# Test_Eagle_File_Sch.net
KiCad netlist of a schematic drawn in EAGLE
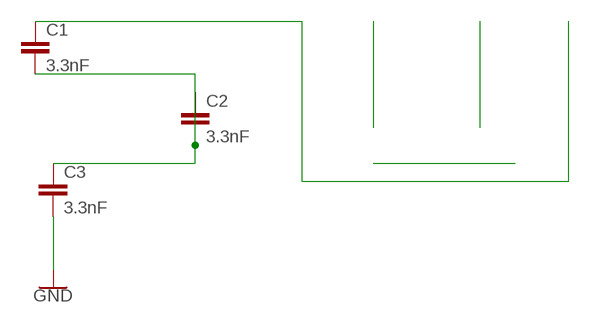
[diagram p0: schematic, sheet 1]
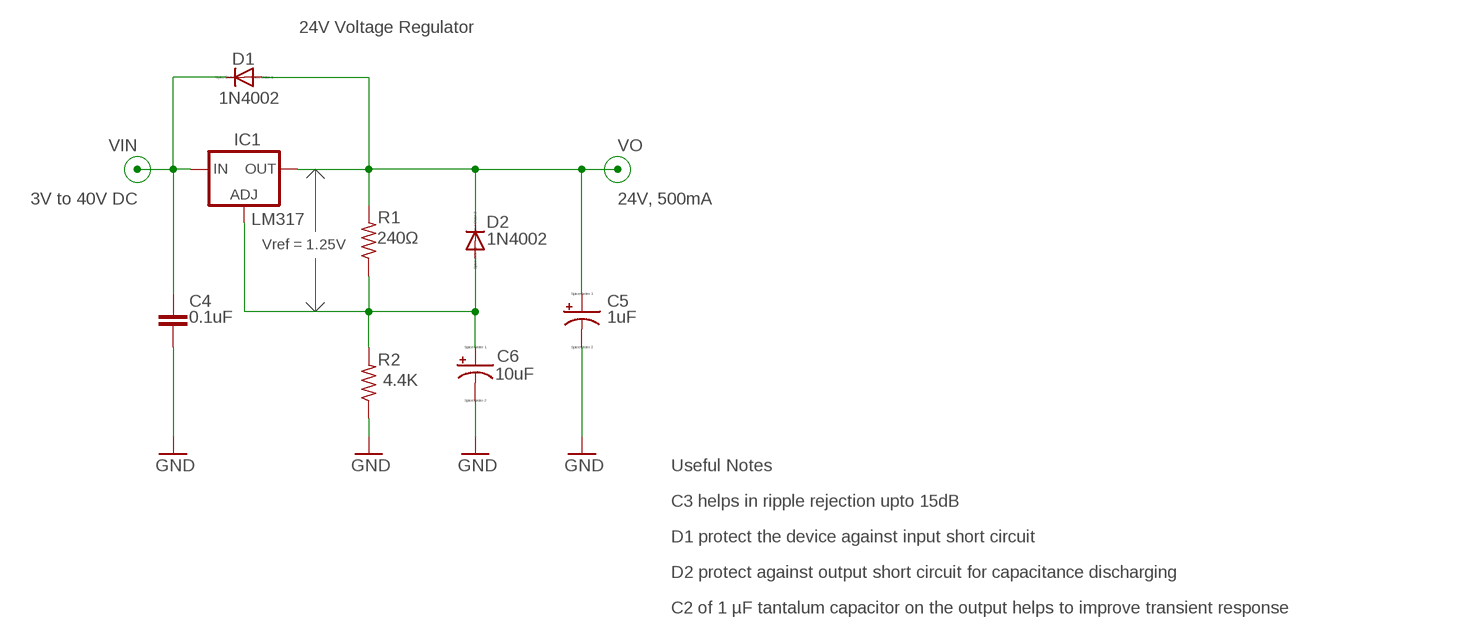
[diagram p1: schematic, sheet 2]

(export (version "E")
  (design (tool "Eeschema 10.0.6"))
  (components
    (comp (ref "C4")
      (value "0.1uF")
      (footprint "eagle-import:C075-052X106")
      (libsource (lib "eagle-import") (part "C-EU075-052X106"))
    )
    (comp (ref "C5")
      (value "1uF")
      (footprint "eagle-import:085CS_1AR")
      (libsource (lib "eagle-import") (part "CPOL-US085CS-1AR"))
    )
    (comp (ref "C6")
      (value "10uF")
      (footprint "eagle-import:085CS_1AR")
      (libsource (lib "eagle-import") (part "CPOL-US085CS-1AR"))
    )
    (comp (ref "D1")
      (value "1N4002")
      (footprint "eagle-import:DO41-10")
      (libsource (lib "eagle-import") (part "1N4004"))
    )
    (comp (ref "D2")
      (value "1N4002")
      (footprint "eagle-import:DO41-10")
      (libsource (lib "eagle-import") (part "1N4004"))
    )
    (comp (ref "IC1")
      (value "LM317MBSTT3")
      (footprint "eagle-import:SOT223")
      (fields (field (name "PARTNUMBER") "LM317"))
      (libsource (lib "eagle-import") (part "LM317?MBSTT3"))
    )
    (comp (ref "R1")
      (value "240Ω")
      (footprint "eagle-import:M0805")
      (libsource (lib "eagle-import") (part "R-US_M0805"))
    )
    (comp (ref "R2")
      (value "4.4K")
      (footprint "eagle-import:M0805")
      (libsource (lib "eagle-import") (part "R-US_M0805"))
    )
    (comp (ref "C1")
      (value "3.3nF")
      (footprint "eagle-import:0603")
      (libsource (lib "eagle-import") (part "3.3NF-0603-100V-10%"))
    )
    (comp (ref "C2")
      (value "3.3nF")
      (footprint "eagle-import:0603")
      (libsource (lib "eagle-import") (part "3.3NF-0603-100V-10%"))
    )
    (comp (ref "C3")
      (value "3.3nF")
      (footprint "eagle-import:0603")
      (libsource (lib "eagle-import") (part "3.3NF-0603-100V-10%"))
    )
  )
  (nets
    (net (code "1") (name "GND") (class "Default")
      (node (ref "C3") (pin "2") (pinfunction "2_2") (pintype "passive"))
      (node (ref "C4") (pin "2") (pinfunction "2_2") (pintype "passive"))
      (node (ref "C5") (pin "-") (pinfunction "-_-") (pintype "passive"))
      (node (ref "C6") (pin "-") (pinfunction "-_-") (pintype "passive"))
      (node (ref "R2") (pin "1") (pinfunction "1_1") (pintype "passive"))
    )
    (net (code "2") (name "Net-(C1-Pad2)") (class "Default")
      (node (ref "C1") (pin "2") (pinfunction "2_2") (pintype "passive"))
      (node (ref "C2") (pin "2") (pinfunction "2_2") (pintype "passive"))
      (node (ref "C3") (pin "1") (pinfunction "1_1") (pintype "passive"))
    )
    (net (code "3") (name "Net-(IC1-ADJ)") (class "Default")
      (node (ref "C6") (pin "+") (pinfunction "+_+") (pintype "passive"))
      (node (ref "D2") (pin "A") (pinfunction "A_A") (pintype "passive"))
      (node (ref "IC1") (pin "1") (pinfunction "ADJ_1") (pintype "input"))
      (node (ref "R1") (pin "1") (pinfunction "1_1") (pintype "passive"))
      (node (ref "R2") (pin "2") (pinfunction "2_2") (pintype "passive"))
    )
    (net (code "4") (name "VIN") (class "Default")
      (node (ref "C4") (pin "1") (pinfunction "1_1") (pintype "passive"))
      (node (ref "D1") (pin "C") (pinfunction "C_C") (pintype "passive"))
      (node (ref "IC1") (pin "3") (pinfunction "IN_3") (pintype "input"))
    )
    (net (code "5") (name "VO") (class "Default")
      (node (ref "C5") (pin "+") (pinfunction "+_+") (pintype "passive"))
      (node (ref "D1") (pin "A") (pinfunction "A_A") (pintype "passive"))
      (node (ref "D2") (pin "C") (pinfunction "C_C") (pintype "passive"))
      (node (ref "IC1") (pin "4") (pinfunction "OUT_4") (pintype "passive"))
      (node (ref "R1") (pin "2") (pinfunction "2_2") (pintype "passive"))
    )
    (net (code "6") (name "unconnected-(C1-Pad1)") (class "Default")
      (node (ref "C1") (pin "1") (pinfunction "1_1") (pintype "passive"))
    )
    (net (code "7") (name "unconnected-(C2-Pad1)") (class "Default")
      (node (ref "C2") (pin "1") (pinfunction "1_1") (pintype "passive"))
    )
  )
)
